# Sheet2.net
KiCad netlist of a schematic drawn in Altium Designer
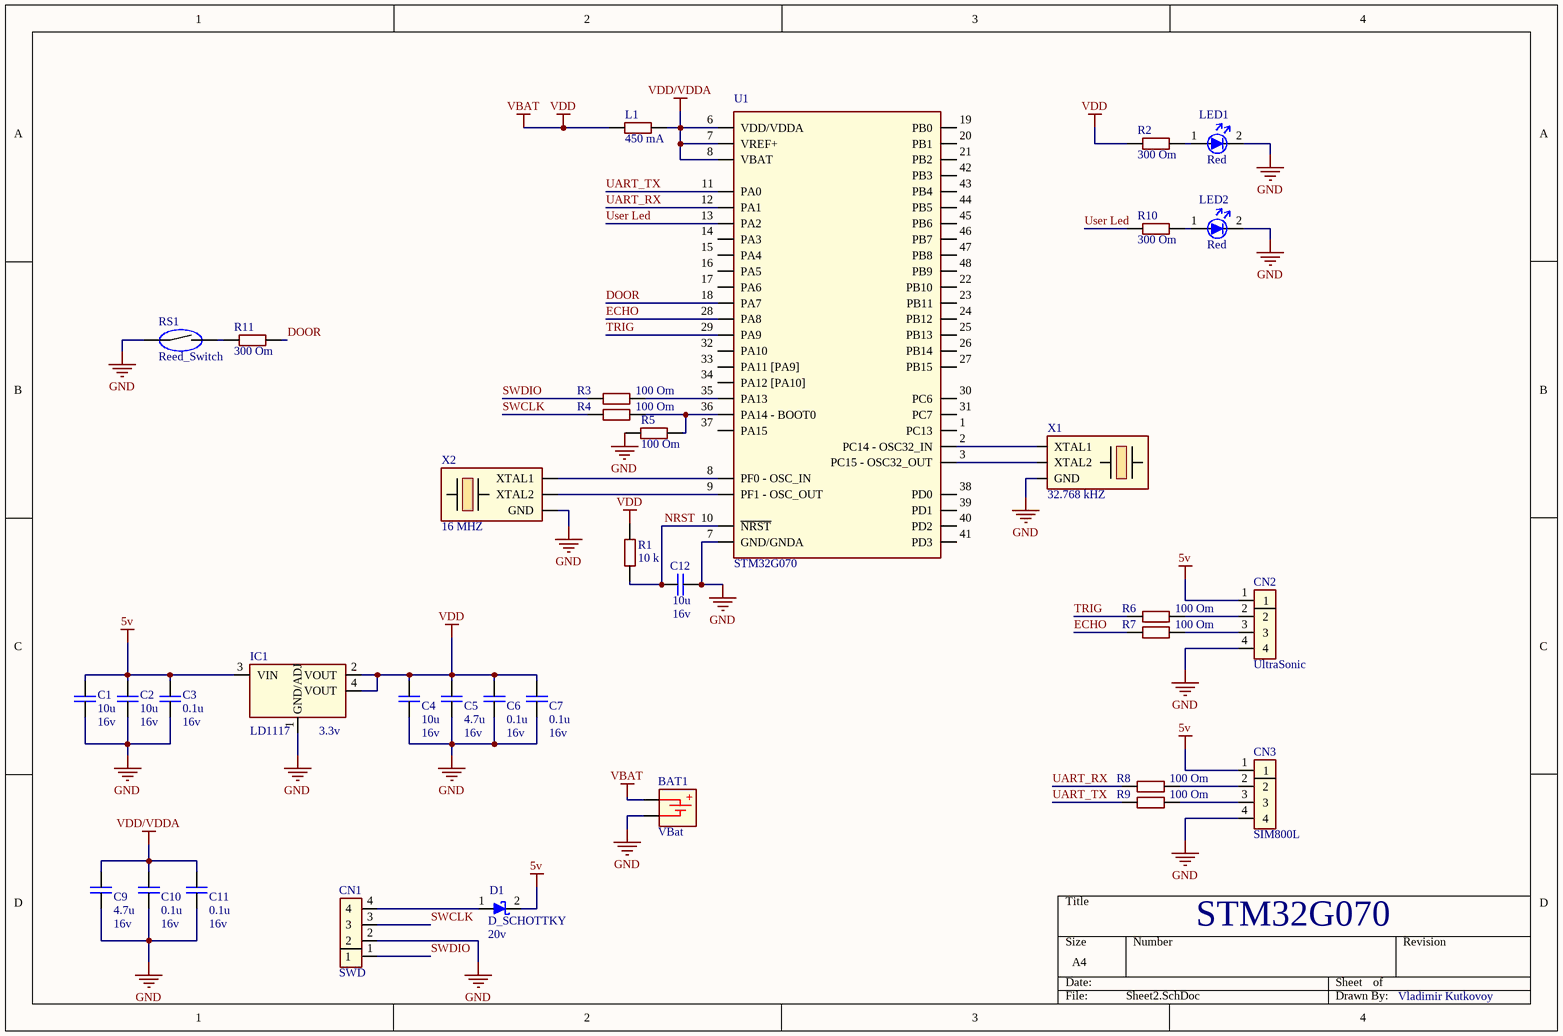
[diagram p0: Sheet2.SchDoc]

(export (version "E")
  (design (tool "Eeschema 10.0.6"))
  (components
    (comp (ref "BAT1") (value "VBat") (footprint "Vbat") (libsource (lib "VK_Lib") (part "VBat")))
    (comp (ref "C1")
      (value "Capacitor")
      (footprint "Capacitor_smd_0863")
      (fields (field (name "СAPACITY") "10u") (field (name "VOLTAGE") "16v"))
      (libsource (lib "VK_Lib") (part "Capacitor"))
    )
    (comp (ref "C2")
      (value "Capacitor")
      (footprint "Capacitor_smd_0863")
      (fields (field (name "СAPACITY") "10u") (field (name "VOLTAGE") "16v"))
      (libsource (lib "VK_Lib") (part "Capacitor"))
    )
    (comp (ref "C3")
      (value "Capacitor")
      (footprint "Capacitor_smd_0863")
      (fields (field (name "СAPACITY") "0.1u") (field (name "VOLTAGE") "16v"))
      (libsource (lib "VK_Lib") (part "Capacitor"))
    )
    (comp (ref "C4")
      (value "Capacitor")
      (footprint "Capacitor_smd_0863")
      (fields (field (name "СAPACITY") "10u") (field (name "VOLTAGE") "16v"))
      (libsource (lib "VK_Lib") (part "Capacitor"))
    )
    (comp (ref "C5")
      (value "Capacitor")
      (footprint "Capacitor_smd_0863")
      (fields (field (name "СAPACITY") "4.7u") (field (name "VOLTAGE") "16v"))
      (libsource (lib "VK_Lib") (part "Capacitor"))
    )
    (comp (ref "C6")
      (value "Capacitor")
      (footprint "Capacitor_smd_0863")
      (fields (field (name "СAPACITY") "0.1u") (field (name "VOLTAGE") "16v"))
      (libsource (lib "VK_Lib") (part "Capacitor"))
    )
    (comp (ref "C7")
      (value "Capacitor")
      (footprint "Capacitor_smd_0863")
      (fields (field (name "СAPACITY") "0.1u") (field (name "VOLTAGE") "16v"))
      (libsource (lib "VK_Lib") (part "Capacitor"))
    )
    (comp (ref "C9")
      (value "Capacitor")
      (footprint "Capacitor_smd_0863")
      (fields (field (name "СAPACITY") "4.7u") (field (name "VOLTAGE") "16v"))
      (libsource (lib "VK_Lib") (part "Capacitor"))
    )
    (comp (ref "C10")
      (value "Capacitor")
      (footprint "Capacitor_smd_0863")
      (fields (field (name "СAPACITY") "0.1u") (field (name "VOLTAGE") "16v"))
      (libsource (lib "VK_Lib") (part "Capacitor"))
    )
    (comp (ref "C11")
      (value "Capacitor")
      (footprint "Capacitor_smd_0863")
      (fields (field (name "СAPACITY") "0.1u") (field (name "VOLTAGE") "16v"))
      (libsource (lib "VK_Lib") (part "Capacitor"))
    )
    (comp (ref "C12")
      (value "Capacitor")
      (footprint "Capacitor_smd_0863")
      (fields (field (name "СAPACITY") "10u") (field (name "VOLTAGE") "16v"))
      (libsource (lib "VK_Lib") (part "Capacitor"))
    )
    (comp (ref "CN1")
      (value "SWD")
      (footprint "Connector_Prog")
      (libsource (lib "") (part "Connector_programming_1"))
    )
    (comp (ref "CN2")
      (value "UltraSonic")
      (footprint "Connector_Prog")
      (libsource (lib "VK_Lib") (part "Connector_programming"))
    )
    (comp (ref "CN3")
      (value "SIM800L")
      (footprint "Connector_Prog")
      (libsource (lib "VK_Lib") (part "Connector_programming"))
    )
    (comp (ref "D1")
      (value "D_SCHOTTKY")
      (footprint "Diod_Shottky")
      (fields (field (name "VOLTAGE") "20v"))
      (libsource (lib "VK_Lib") (part "Diod_Shottky"))
    )
    (comp (ref "IC1")
      (value "LD1117")
      (footprint "LD1117")
      (fields (field (name "VOLTAGE") "3.3v"))
      (libsource (lib "VK_Lib") (part "LD1117"))
    )
    (comp (ref "L1")
      (value "450 mA")
      (footprint "Resistor_smd_0603")
      (libsource (lib "VK_Lib") (part "Filter"))
    )
    (comp (ref "LED1") (value "Red") (footprint "Led_smd_0603_Red") (libsource (lib "VK_Lib") (part "LED")))
    (comp (ref "LED2") (value "Red") (footprint "Led_smd_0603_Red") (libsource (lib "VK_Lib") (part "LED")))
    (comp (ref "R1") (value "10 k") (footprint "Resistor_smd_0603") (libsource (lib "") (part "Resistor_1")))
    (comp (ref "R2")
      (value "300 Om")
      (footprint "Resistor_smd_0603")
      (libsource (lib "VK_Lib") (part "Resistor"))
    )
    (comp (ref "R3")
      (value "100 Om")
      (footprint "Resistor_smd_0603")
      (libsource (lib "VK_Lib") (part "Resistor"))
    )
    (comp (ref "R4")
      (value "100 Om")
      (footprint "Resistor_smd_0603")
      (libsource (lib "VK_Lib") (part "Resistor"))
    )
    (comp (ref "R5")
      (value "100 Om")
      (footprint "Resistor_smd_0603")
      (libsource (lib "VK_Lib") (part "Resistor"))
    )
    (comp (ref "R6")
      (value "100 Om")
      (footprint "Resistor_smd_0603")
      (libsource (lib "VK_Lib") (part "Resistor"))
    )
    (comp (ref "R7")
      (value "100 Om")
      (footprint "Resistor_smd_0603")
      (libsource (lib "VK_Lib") (part "Resistor"))
    )
    (comp (ref "R8")
      (value "100 Om")
      (footprint "Resistor_smd_0603")
      (libsource (lib "VK_Lib") (part "Resistor"))
    )
    (comp (ref "R9")
      (value "100 Om")
      (footprint "Resistor_smd_0603")
      (libsource (lib "VK_Lib") (part "Resistor"))
    )
    (comp (ref "R10")
      (value "300 Om")
      (footprint "Resistor_smd_0603")
      (libsource (lib "VK_Lib") (part "Resistor"))
    )
    (comp (ref "R11")
      (value "300 Om")
      (footprint "Resistor_smd_0603")
      (libsource (lib "VK_Lib") (part "Resistor"))
    )
    (comp (ref "RS1")
      (value "Reed_Switch")
      (footprint "Vbat")
      (libsource (lib "VK_Lib") (part "Reed_Switch"))
    )
    (comp (ref "U1")
      (value "STM32G070")
      (footprint "STM32G070")
      (libsource (lib "VK_Lib") (part "STM32G070"))
    )
    (comp (ref "X1") (value "32.768 kHZ") (libsource (lib "VK_Lib") (part "XTAL")))
    (comp (ref "X2") (value "16 MHZ") (libsource (lib "VK_Lib") (part "XTAL_RightPin")))
  )
  (nets
    (net (code "1") (name "/DOOR") (class "Default")
      (node (ref "R11") (pin "2") (pinfunction "2_2") (pintype "passive"))
      (node (ref "U1") (pin "18") (pinfunction "PA7_18") (pintype "passive"))
    )
    (net (code "2") (name "/ECHO") (class "Default")
      (node (ref "R7") (pin "1") (pinfunction "1_1") (pintype "passive"))
      (node (ref "U1") (pin "28") (pinfunction "PA8_28") (pintype "passive"))
    )
    (net (code "3") (name "/NRST") (class "Default")
      (node (ref "C12") (pin "2") (pinfunction "2_2") (pintype "passive"))
      (node (ref "R1") (pin "1") (pinfunction "1_1") (pintype "passive"))
      (node (ref "U1") (pin "10") (pinfunction "~{NRST}_10") (pintype "passive"))
    )
    (net (code "4") (name "/SWCLK") (class "Default")
      (node (ref "CN1") (pin "3") (pinfunction "3_3") (pintype "passive"))
      (node (ref "R4") (pin "1") (pinfunction "1_1") (pintype "passive"))
    )
    (net (code "5") (name "/SWDIO") (class "Default")
      (node (ref "CN1") (pin "1") (pinfunction "1_1") (pintype "passive"))
      (node (ref "R3") (pin "1") (pinfunction "1_1") (pintype "passive"))
    )
    (net (code "6") (name "/TRIG") (class "Default")
      (node (ref "R6") (pin "1") (pinfunction "1_1") (pintype "passive"))
      (node (ref "U1") (pin "29") (pinfunction "PA9_29") (pintype "passive"))
    )
    (net (code "7") (name "/UART_RX") (class "Default")
      (node (ref "R8") (pin "1") (pinfunction "1_1") (pintype "passive"))
      (node (ref "U1") (pin "12") (pinfunction "PA1_12") (pintype "passive"))
    )
    (net (code "8") (name "/UART_TX") (class "Default")
      (node (ref "R9") (pin "1") (pinfunction "1_1") (pintype "passive"))
      (node (ref "U1") (pin "11") (pinfunction "PA0_11") (pintype "passive"))
    )
    (net (code "9") (name "/User Led") (class "Default")
      (node (ref "R10") (pin "1") (pinfunction "1_1") (pintype "passive"))
      (node (ref "U1") (pin "13") (pinfunction "PA2_13") (pintype "passive"))
    )
    (net (code "10") (name "5v") (class "Default")
      (node (ref "C1") (pin "1") (pinfunction "1_1") (pintype "passive"))
      (node (ref "C2") (pin "1") (pinfunction "1_1") (pintype "passive"))
      (node (ref "C3") (pin "1") (pinfunction "1_1") (pintype "passive"))
      (node (ref "CN2") (pin "1") (pinfunction "1_1") (pintype "passive"))
      (node (ref "CN3") (pin "1") (pinfunction "1_1") (pintype "passive"))
      (node (ref "D1") (pin "2") (pinfunction "2_2") (pintype "passive"))
      (node (ref "IC1") (pin "3") (pinfunction "VIN_3") (pintype "passive"))
    )
    (net (code "11") (name "GND") (class "Default")
      (node (ref "BAT1") (pin "2") (pinfunction "GND_2") (pintype "passive"))
      (node (ref "C1") (pin "2") (pinfunction "2_2") (pintype "passive"))
      (node (ref "C10") (pin "1") (pinfunction "1_1") (pintype "passive"))
      (node (ref "C11") (pin "1") (pinfunction "1_1") (pintype "passive"))
      (node (ref "C12") (pin "1") (pinfunction "1_1") (pintype "passive"))
      (node (ref "C2") (pin "2") (pinfunction "2_2") (pintype "passive"))
      (node (ref "C3") (pin "2") (pinfunction "2_2") (pintype "passive"))
      (node (ref "C4") (pin "1") (pinfunction "1_1") (pintype "passive"))
      (node (ref "C5") (pin "1") (pinfunction "1_1") (pintype "passive"))
      (node (ref "C6") (pin "1") (pinfunction "1_1") (pintype "passive"))
      (node (ref "C7") (pin "1") (pinfunction "1_1") (pintype "passive"))
      (node (ref "C9") (pin "1") (pinfunction "1_1") (pintype "passive"))
      (node (ref "CN1") (pin "2") (pinfunction "2_2") (pintype "passive"))
      (node (ref "CN2") (pin "4") (pinfunction "4_4") (pintype "passive"))
      (node (ref "CN3") (pin "4") (pinfunction "4_4") (pintype "passive"))
      (node (ref "IC1") (pin "1") (pinfunction "GND/ADJ_1") (pintype "passive"))
      (node (ref "LED1") (pin "2") (pinfunction "2_2") (pintype "passive"))
      (node (ref "LED2") (pin "2") (pinfunction "2_2") (pintype "passive"))
      (node (ref "R5") (pin "1") (pinfunction "1_1") (pintype "passive"))
      (node (ref "RS1") (pin "1") (pinfunction "1_1") (pintype "passive"))
      (node (ref "U1") (pin "7") (pinfunction "GND/GNDA_7") (pintype "power_in"))
      (node (ref "X1") (pin "3") (pinfunction "GND_3") (pintype "passive"))
      (node (ref "X2") (pin "3") (pinfunction "GND_3") (pintype "passive"))
    )
    (net (code "12") (name "Net-(CN1-Pad4)") (class "Default")
      (node (ref "CN1") (pin "4") (pinfunction "4_4") (pintype "passive"))
      (node (ref "D1") (pin "1") (pinfunction "1_1") (pintype "passive"))
    )
    (net (code "13") (name "Net-(CN2-Pad2)") (class "Default")
      (node (ref "CN2") (pin "2") (pinfunction "2_2") (pintype "passive"))
      (node (ref "R6") (pin "2") (pinfunction "2_2") (pintype "passive"))
    )
    (net (code "14") (name "Net-(CN2-Pad3)") (class "Default")
      (node (ref "CN2") (pin "3") (pinfunction "3_3") (pintype "passive"))
      (node (ref "R7") (pin "2") (pinfunction "2_2") (pintype "passive"))
    )
    (net (code "15") (name "Net-(CN3-Pad2)") (class "Default")
      (node (ref "CN3") (pin "2") (pinfunction "2_2") (pintype "passive"))
      (node (ref "R8") (pin "2") (pinfunction "2_2") (pintype "passive"))
    )
    (net (code "16") (name "Net-(CN3-Pad3)") (class "Default")
      (node (ref "CN3") (pin "3") (pinfunction "3_3") (pintype "passive"))
      (node (ref "R9") (pin "2") (pinfunction "2_2") (pintype "passive"))
    )
    (net (code "17") (name "Net-(LED1-Pad1)") (class "Default")
      (node (ref "LED1") (pin "1") (pinfunction "1_1") (pintype "passive"))
      (node (ref "R2") (pin "2") (pinfunction "2_2") (pintype "passive"))
    )
    (net (code "18") (name "Net-(LED2-Pad1)") (class "Default")
      (node (ref "LED2") (pin "1") (pinfunction "1_1") (pintype "passive"))
      (node (ref "R10") (pin "2") (pinfunction "2_2") (pintype "passive"))
    )
    (net (code "19") (name "Net-(R11-Pad1)") (class "Default")
      (node (ref "R11") (pin "1") (pinfunction "1_1") (pintype "passive"))
      (node (ref "RS1") (pin "2") (pinfunction "2_2") (pintype "passive"))
    )
    (net (code "20") (name "Net-(U1-PA13)") (class "Default")
      (node (ref "R3") (pin "2") (pinfunction "2_2") (pintype "passive"))
      (node (ref "U1") (pin "35") (pinfunction "PA13_35") (pintype "passive"))
    )
    (net (code "21") (name "Net-(U1-PA14_-_BOOT0)") (class "Default")
      (node (ref "R4") (pin "2") (pinfunction "2_2") (pintype "passive"))
      (node (ref "R5") (pin "2") (pinfunction "2_2") (pintype "passive"))
      (node (ref "U1") (pin "36") (pinfunction "PA14_-_BOOT0_36") (pintype "passive"))
    )
    (net (code "22") (name "Net-(U1-PC14_-_OSC32_IN)") (class "Default")
      (node (ref "U1") (pin "2") (pinfunction "PC14_-_OSC32_IN_2") (pintype "passive"))
      (node (ref "X1") (pin "1") (pinfunction "XTAL1_1") (pintype "passive"))
    )
    (net (code "23") (name "Net-(U1-PC15_-_OSC32_OUT)") (class "Default")
      (node (ref "U1") (pin "3") (pinfunction "PC15_-_OSC32_OUT_3") (pintype "passive"))
      (node (ref "X1") (pin "2") (pinfunction "XTAL2_2") (pintype "passive"))
    )
    (net (code "24") (name "Net-(U1-PF0_-_OSC_IN)") (class "Default")
      (node (ref "U1") (pin "8") (pinfunction "PF0_-_OSC_IN_8") (pintype "passive"))
      (node (ref "X2") (pin "1") (pinfunction "XTAL1_1") (pintype "passive"))
    )
    (net (code "25") (name "Net-(U1-PF1_-_OSC_OUT)") (class "Default")
      (node (ref "U1") (pin "9") (pinfunction "PF1_-_OSC_OUT_9") (pintype "passive"))
      (node (ref "X2") (pin "2") (pinfunction "XTAL2_2") (pintype "passive"))
    )
    (net (code "26") (name "VBAT") (class "Default")
      (node (ref "BAT1") (pin "1") (pinfunction "VCC_1") (pintype "passive"))
      (node (ref "C4") (pin "2") (pinfunction "2_2") (pintype "passive"))
      (node (ref "C5") (pin "2") (pinfunction "2_2") (pintype "passive"))
      (node (ref "C6") (pin "2") (pinfunction "2_2") (pintype "passive"))
      (node (ref "C7") (pin "2") (pinfunction "2_2") (pintype "passive"))
      (node (ref "IC1") (pin "2") (pinfunction "VOUT_2") (pintype "passive"))
      (node (ref "IC1") (pin "4") (pinfunction "VOUT_4") (pintype "passive"))
      (node (ref "L1") (pin "1") (pinfunction "1_1") (pintype "passive"))
      (node (ref "R1") (pin "2") (pinfunction "2_2") (pintype "passive"))
      (node (ref "R2") (pin "1") (pinfunction "1_1") (pintype "passive"))
    )
    (net (code "27") (name "VDD{slash}VDDA") (class "Default")
      (node (ref "C10") (pin "2") (pinfunction "2_2") (pintype "passive"))
      (node (ref "C11") (pin "2") (pinfunction "2_2") (pintype "passive"))
      (node (ref "C9") (pin "2") (pinfunction "2_2") (pintype "passive"))
      (node (ref "L1") (pin "2") (pinfunction "2_2") (pintype "passive"))
      (node (ref "U1") (pin "6") (pinfunction "VDD/VDDA_6") (pintype "power_in"))
      (node (ref "U1") (pin "7") (pinfunction "VREF+_7") (pintype "power_in"))
      (node (ref "U1") (pin "8") (pinfunction "VBAT_8") (pintype "power_in"))
    )
    (net (code "28") (name "unconnected-(U1-PA3-Pad14)") (class "Default")
      (node (ref "U1") (pin "14") (pinfunction "PA3_14") (pintype "passive"))
    )
    (net (code "29") (name "unconnected-(U1-PA4-Pad15)") (class "Default")
      (node (ref "U1") (pin "15") (pinfunction "PA4_15") (pintype "passive"))
    )
    (net (code "30") (name "unconnected-(U1-PA5-Pad16)") (class "Default")
      (node (ref "U1") (pin "16") (pinfunction "PA5_16") (pintype "passive"))
    )
    (net (code "31") (name "unconnected-(U1-PA6-Pad17)") (class "Default")
      (node (ref "U1") (pin "17") (pinfunction "PA6_17") (pintype "passive"))
    )
    (net (code "32") (name "unconnected-(U1-PA10-Pad32)") (class "Default")
      (node (ref "U1") (pin "32") (pinfunction "PA10_32") (pintype "passive"))
    )
    (net (code "33") (name "unconnected-(U1-PA11_[PA9]-Pad33)") (class "Default")
      (node (ref "U1") (pin "33") (pinfunction "PA11_[PA9]_33") (pintype "passive"))
    )
    (net (code "34") (name "unconnected-(U1-PA12_[PA10]-Pad34)") (class "Default")
      (node (ref "U1") (pin "34") (pinfunction "PA12_[PA10]_34") (pintype "passive"))
    )
    (net (code "35") (name "unconnected-(U1-PA15-Pad37)") (class "Default")
      (node (ref "U1") (pin "37") (pinfunction "PA15_37") (pintype "passive"))
    )
    (net (code "36") (name "unconnected-(U1-PB0-Pad19)") (class "Default")
      (node (ref "U1") (pin "19") (pinfunction "PB0_19") (pintype "passive"))
    )
    (net (code "37") (name "unconnected-(U1-PB1-Pad20)") (class "Default")
      (node (ref "U1") (pin "20") (pinfunction "PB1_20") (pintype "passive"))
    )
    (net (code "38") (name "unconnected-(U1-PB2-Pad21)") (class "Default")
      (node (ref "U1") (pin "21") (pinfunction "PB2_21") (pintype "passive"))
    )
    (net (code "39") (name "unconnected-(U1-PB3-Pad42)") (class "Default")
      (node (ref "U1") (pin "42") (pinfunction "PB3_42") (pintype "passive"))
    )
    (net (code "40") (name "unconnected-(U1-PB4-Pad43)") (class "Default")
      (node (ref "U1") (pin "43") (pinfunction "PB4_43") (pintype "passive"))
    )
    (net (code "41") (name "unconnected-(U1-PB5-Pad44)") (class "Default")
      (node (ref "U1") (pin "44") (pinfunction "PB5_44") (pintype "passive"))
    )
    (net (code "42") (name "unconnected-(U1-PB6-Pad45)") (class "Default")
      (node (ref "U1") (pin "45") (pinfunction "PB6_45") (pintype "passive"))
    )
    (net (code "43") (name "unconnected-(U1-PB7-Pad46)") (class "Default")
      (node (ref "U1") (pin "46") (pinfunction "PB7_46") (pintype "passive"))
    )
    (net (code "44") (name "unconnected-(U1-PB8-Pad47)") (class "Default")
      (node (ref "U1") (pin "47") (pinfunction "PB8_47") (pintype "passive"))
    )
    (net (code "45") (name "unconnected-(U1-PB9-Pad48)") (class "Default")
      (node (ref "U1") (pin "48") (pinfunction "PB9_48") (pintype "passive"))
    )
    (net (code "46") (name "unconnected-(U1-PB10-Pad22)") (class "Default")
      (node (ref "U1") (pin "22") (pinfunction "PB10_22") (pintype "passive"))
    )
    (net (code "47") (name "unconnected-(U1-PB11-Pad23)") (class "Default")
      (node (ref "U1") (pin "23") (pinfunction "PB11_23") (pintype "passive"))
    )
    (net (code "48") (name "unconnected-(U1-PB12-Pad24)") (class "Default")
      (node (ref "U1") (pin "24") (pinfunction "PB12_24") (pintype "passive"))
    )
    (net (code "49") (name "unconnected-(U1-PB13-Pad25)") (class "Default")
      (node (ref "U1") (pin "25") (pinfunction "PB13_25") (pintype "passive"))
    )
    (net (code "50") (name "unconnected-(U1-PB14-Pad26)") (class "Default")
      (node (ref "U1") (pin "26") (pinfunction "PB14_26") (pintype "passive"))
    )
    (net (code "51") (name "unconnected-(U1-PB15-Pad27)") (class "Default")
      (node (ref "U1") (pin "27") (pinfunction "PB15_27") (pintype "passive"))
    )
    (net (code "52") (name "unconnected-(U1-PD0-Pad38)") (class "Default")
      (node (ref "U1") (pin "38") (pinfunction "PD0_38") (pintype "passive"))
    )
    (net (code "53") (name "unconnected-(U1-PD1-Pad39)") (class "Default")
      (node (ref "U1") (pin "39") (pinfunction "PD1_39") (pintype "passive"))
    )
    (net (code "54") (name "unconnected-(U1-PD2-Pad40)") (class "Default")
      (node (ref "U1") (pin "40") (pinfunction "PD2_40") (pintype "passive"))
    )
    (net (code "55") (name "unconnected-(U1-PD3-Pad41)") (class "Default")
      (node (ref "U1") (pin "41") (pinfunction "PD3_41") (pintype "passive"))
    )
    (net (code "56") (name "unconnected-(U1-PС6-Pad30)") (class "Default")
      (node (ref "U1") (pin "30") (pinfunction "PС6_30") (pintype "passive"))
    )
    (net (code "57") (name "unconnected-(U1-PС7-Pad31)") (class "Default")
      (node (ref "U1") (pin "31") (pinfunction "PС7_31") (pintype "passive"))
    )
    (net (code "58") (name "unconnected-(U1-PС13-Pad1)") (class "Default")
      (node (ref "U1") (pin "1") (pinfunction "PС13_1") (pintype "passive"))
    )
  )
)
